# v0_1_0.net
KiCad netlist of a schematic drawn in EAGLE
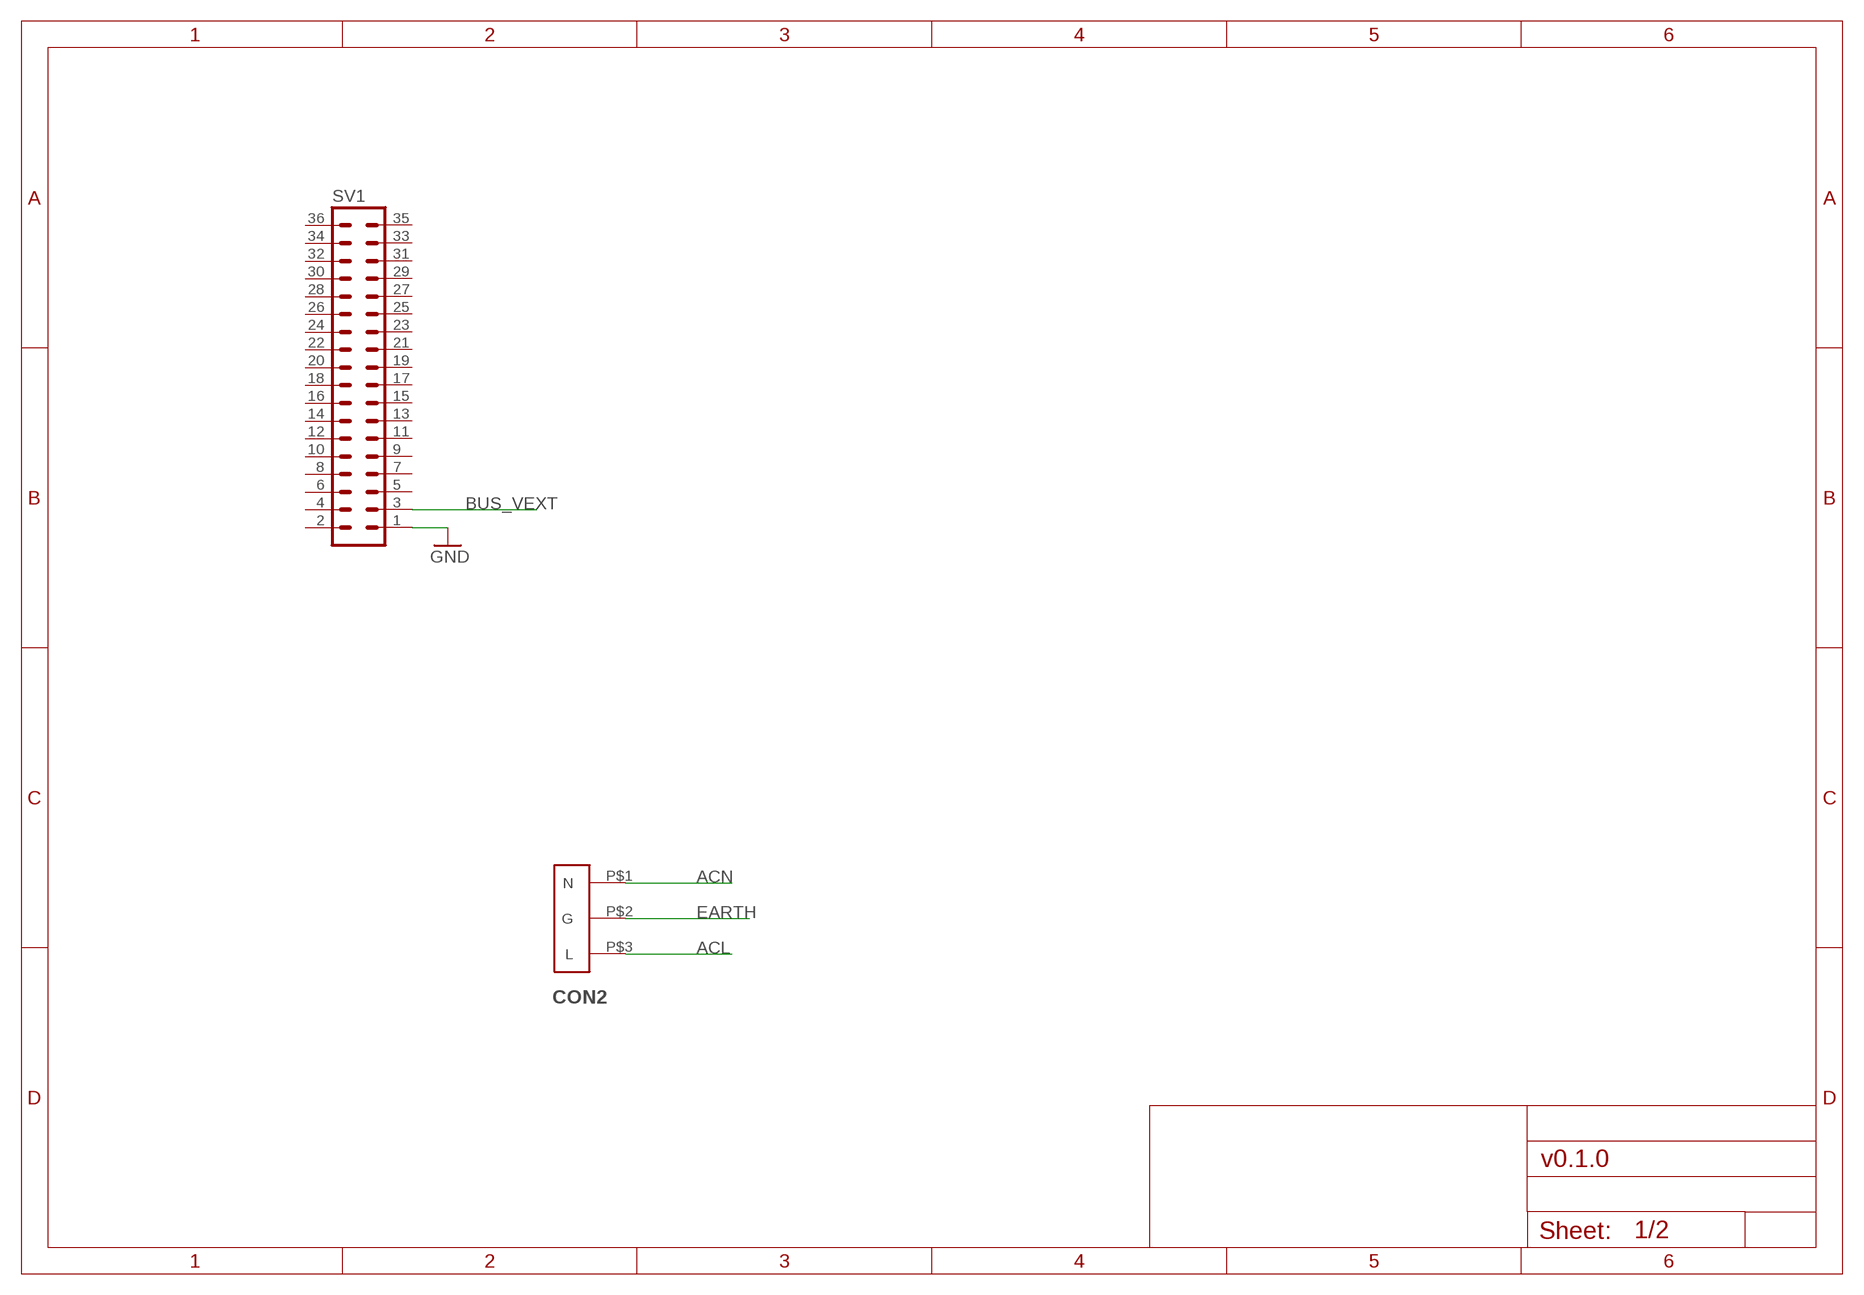
[diagram p0: schematic, sheet 1]
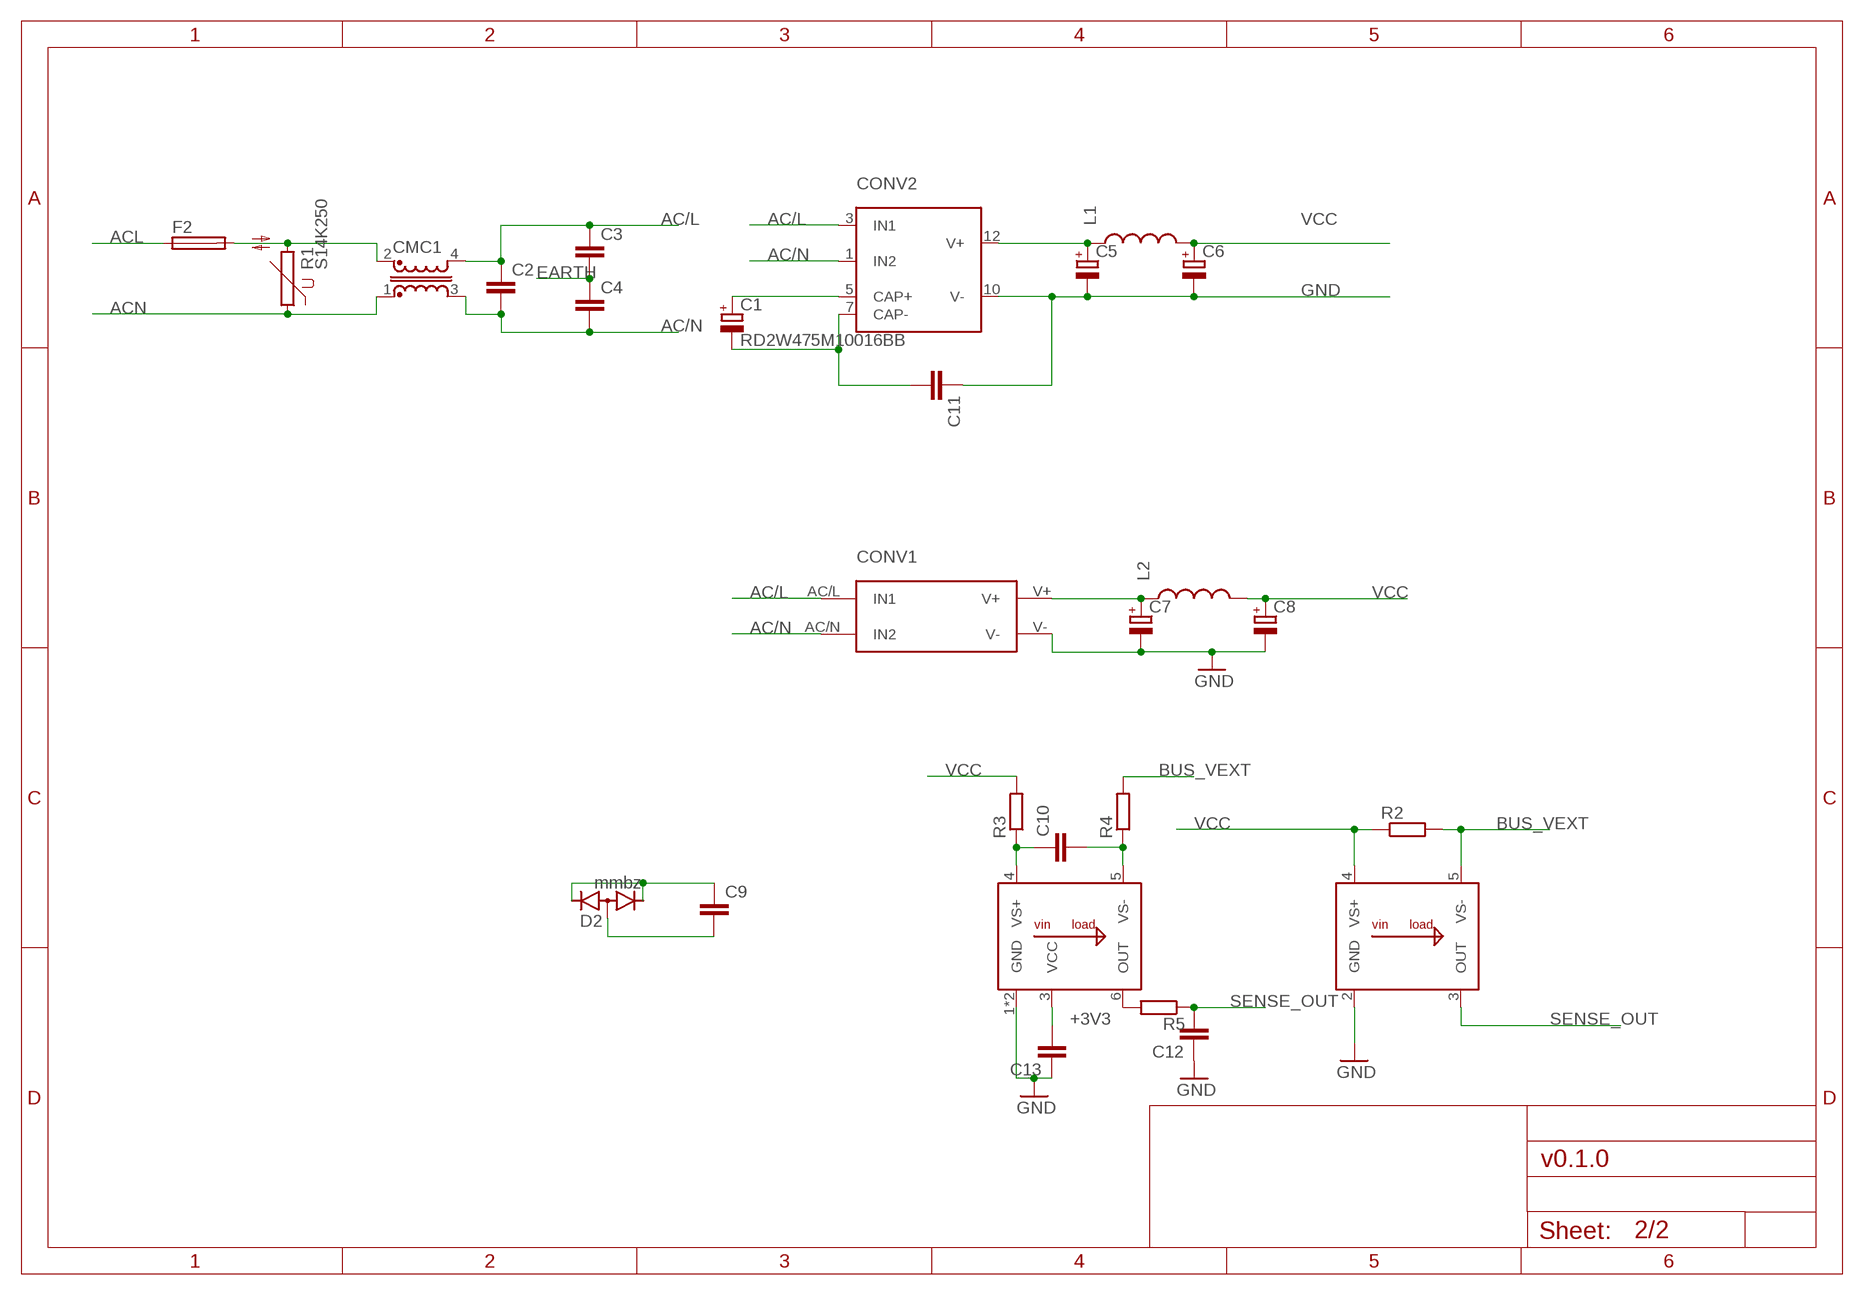
[diagram p1: schematic, sheet 2]

(export (version "E")
  (design (tool "Eeschema 10.0.6"))
  (components
    (comp (ref "C1")
      (value "RD2W475M10016BB")
      (footprint "eagle-import:E5-10,5")
      (libsource (lib "eagle-import") (part "CPOL-EUE5-10.5"))
    )
    (comp (ref "C2")
      (value "C-EUC1206")
      (footprint "eagle-import:C1206")
      (libsource (lib "eagle-import") (part "C-EUC1206"))
    )
    (comp (ref "C3")
      (value "C-EUC1206")
      (footprint "eagle-import:C1206")
      (libsource (lib "eagle-import") (part "C-EUC1206"))
    )
    (comp (ref "C4")
      (value "C-EUC1206")
      (footprint "eagle-import:C1206")
      (libsource (lib "eagle-import") (part "C-EUC1206"))
    )
    (comp (ref "C5")
      (value "CPOL-EUE5-10.5")
      (footprint "eagle-import:E5-10,5")
      (libsource (lib "eagle-import") (part "CPOL-EUE5-10.5"))
    )
    (comp (ref "C6")
      (value "CPOL-EUE5-10.5")
      (footprint "eagle-import:E5-10,5")
      (libsource (lib "eagle-import") (part "CPOL-EUE5-10.5"))
    )
    (comp (ref "C7")
      (value "CPOL-EUE5-10.5")
      (footprint "eagle-import:E5-10,5")
      (libsource (lib "eagle-import") (part "CPOL-EUE5-10.5"))
    )
    (comp (ref "C8")
      (value "CPOL-EUE5-10.5")
      (footprint "eagle-import:E5-10,5")
      (libsource (lib "eagle-import") (part "CPOL-EUE5-10.5"))
    )
    (comp (ref "C9")
      (value "C-EUC1206")
      (footprint "eagle-import:C1206")
      (libsource (lib "eagle-import") (part "C-EUC1206"))
    )
    (comp (ref "C10")
      (value "C-EUC0402")
      (footprint "eagle-import:C0402")
      (libsource (lib "eagle-import") (part "C-EUC0402"))
    )
    (comp (ref "C11")
      (value "C-EUC1206")
      (footprint "eagle-import:C1206")
      (libsource (lib "eagle-import") (part "C-EUC1206"))
    )
    (comp (ref "C12")
      (value "C-EUC0402")
      (footprint "eagle-import:C0402")
      (libsource (lib "eagle-import") (part "C-EUC0402"))
    )
    (comp (ref "C13")
      (value "C-EUC0402")
      (footprint "eagle-import:C0402")
      (libsource (lib "eagle-import") (part "C-EUC0402"))
    )
    (comp (ref "CMC1")
      (value "DLD-302U-1A")
      (footprint "eagle-import:DLD")
      (libsource (lib "eagle-import") (part "DLD-302U-1A"))
    )
    (comp (ref "CONV1")
      (value "IRM-03-12V")
      (footprint "eagle-import:IRM-03")
      (libsource (lib "eagle-import") (part "IRM-03-12V"))
    )
    (comp (ref "CONV2")
      (value "AMEOF312SJZ")
      (footprint "eagle-import:AMEOF3-JZ")
      (libsource (lib "eagle-import") (part "AMEOF312SJZ"))
    )
    (comp (ref "D2")
      (value "mmbz")
      (footprint "eagle-import:SOT23")
      (libsource (lib "eagle-import") (part "DIODE-2CA|ACSOT23"))
    )
    (comp (ref "F2")
      (value "ZH8")
      (footprint "eagle-import:ZH8X2")
      (libsource (lib "eagle-import") (part "ZH8"))
    )
    (comp (ref "IC1")
      (value "ZXCT1021")
      (footprint "eagle-import:SOT95P240X110-5")
      (libsource (lib "eagle-import") (part "ZXCT1021"))
    )
    (comp (ref "IC2")
      (value "BQ500100")
      (footprint "eagle-import:SC70-6")
      (libsource (lib "eagle-import") (part "BQ500100"))
    )
    (comp (ref "L1")
      (value "COIL0608-0.022")
      (footprint "eagle-import:COIL0608")
      (libsource (lib "eagle-import") (part "COIL0608-0.022"))
    )
    (comp (ref "L2")
      (value "COIL0608-0.022")
      (footprint "eagle-import:COIL0608")
      (libsource (lib "eagle-import") (part "COIL0608-0.022"))
    )
    (comp (ref "R1")
      (value "S14K250")
      (footprint "eagle-import:S14K250")
      (libsource (lib "eagle-import") (part "S14K250"))
    )
    (comp (ref "R2")
      (value "R-EU_R0805")
      (footprint "eagle-import:R0805")
      (libsource (lib "eagle-import") (part "R-EU_R0805"))
    )
    (comp (ref "R3")
      (value "R-EU_R0402")
      (footprint "eagle-import:R0402")
      (libsource (lib "eagle-import") (part "R-EU_R0402"))
    )
    (comp (ref "R4")
      (value "R-EU_R0402")
      (footprint "eagle-import:R0402")
      (libsource (lib "eagle-import") (part "R-EU_R0402"))
    )
    (comp (ref "R5")
      (value "R-EU_R0402")
      (footprint "eagle-import:R0402")
      (libsource (lib "eagle-import") (part "R-EU_R0402"))
    )
    (comp (ref "CON2")
      (value "4300.0101")
      (footprint "eagle-import:IEC-C6")
      (libsource (lib "eagle-import") (part "4300.0101"))
    )
    (comp (ref "SV1")
      (value "MA18-2")
      (footprint "eagle-import:MA18-2")
      (libsource (lib "eagle-import") (part "MA18-2"))
    )
  )
  (nets
    (net (code "1") (name "+3V3") (class "Default")
      (node (ref "C13") (pin "2") (pinfunction "2_2") (pintype "passive"))
      (node (ref "IC2") (pin "3") (pinfunction "VCC_3") (pintype "bidirectional"))
    )
    (net (code "2") (name "ACL") (class "Default")
      (node (ref "CON2") (pin "P$3") (pinfunction "L_P$3") (pintype "bidirectional"))
      (node (ref "F2") (pin "1") (pinfunction "1_1") (pintype "passive"))
      (node (ref "F2") (pin "1A") (pinfunction "1_1A") (pintype "passive"))
    )
    (net (code "3") (name "ACN") (class "Default")
      (node (ref "CMC1") (pin "1") (pinfunction "1_1") (pintype "passive"))
      (node (ref "CON2") (pin "P$1") (pinfunction "N_P$1") (pintype "bidirectional"))
      (node (ref "R1") (pin "1") (pinfunction "1_1") (pintype "passive"))
    )
    (net (code "4") (name "AC{slash}L") (class "Default")
      (node (ref "C2") (pin "1") (pinfunction "1_1") (pintype "passive"))
      (node (ref "C3") (pin "1") (pinfunction "1_1") (pintype "passive"))
      (node (ref "CMC1") (pin "4") (pinfunction "4_4") (pintype "passive"))
      (node (ref "CONV1") (pin "AC/L") (pinfunction "IN1_AC/L") (pintype "bidirectional"))
      (node (ref "CONV2") (pin "3") (pinfunction "IN1_3") (pintype "bidirectional"))
    )
    (net (code "5") (name "AC{slash}N") (class "Default")
      (node (ref "C2") (pin "2") (pinfunction "2_2") (pintype "passive"))
      (node (ref "C4") (pin "2") (pinfunction "2_2") (pintype "passive"))
      (node (ref "CMC1") (pin "3") (pinfunction "3_3") (pintype "passive"))
      (node (ref "CONV1") (pin "AC/N") (pinfunction "IN2_AC/N") (pintype "bidirectional"))
      (node (ref "CONV2") (pin "1") (pinfunction "IN2_1") (pintype "bidirectional"))
    )
    (net (code "6") (name "BUS_VEXT") (class "Default")
      (node (ref "IC1") (pin "5") (pinfunction "VS-_5") (pintype "bidirectional"))
      (node (ref "R2") (pin "2") (pinfunction "2_2") (pintype "passive"))
      (node (ref "R4") (pin "2") (pinfunction "2_2") (pintype "passive"))
      (node (ref "SV1") (pin "3") (pinfunction "3_3") (pintype "passive"))
    )
    (net (code "7") (name "EARTH") (class "Default")
      (node (ref "C3") (pin "2") (pinfunction "2_2") (pintype "passive"))
      (node (ref "C4") (pin "1") (pinfunction "1_1") (pintype "passive"))
      (node (ref "CON2") (pin "P$2") (pinfunction "G_P$2") (pintype "bidirectional"))
    )
    (net (code "8") (name "GND") (class "Default")
      (node (ref "C11") (pin "1") (pinfunction "1_1") (pintype "passive"))
      (node (ref "C12") (pin "1") (pinfunction "1_1") (pintype "passive"))
      (node (ref "C13") (pin "1") (pinfunction "1_1") (pintype "passive"))
      (node (ref "C5") (pin "-") (pinfunction "-_-") (pintype "passive"))
      (node (ref "C6") (pin "-") (pinfunction "-_-") (pintype "passive"))
      (node (ref "C7") (pin "-") (pinfunction "-_-") (pintype "passive"))
      (node (ref "C8") (pin "-") (pinfunction "-_-") (pintype "passive"))
      (node (ref "CONV1") (pin "V-") (pinfunction "V-_V-") (pintype "bidirectional"))
      (node (ref "CONV2") (pin "10") (pinfunction "V-_10") (pintype "bidirectional"))
      (node (ref "IC1") (pin "2") (pinfunction "GND_2") (pintype "bidirectional"))
      (node (ref "IC2") (pin "1") (pinfunction "GND_1") (pintype "bidirectional"))
      (node (ref "IC2") (pin "2") (pinfunction "GND_2") (pintype "bidirectional"))
      (node (ref "SV1") (pin "1") (pinfunction "1_1") (pintype "passive"))
    )
    (net (code "9") (name "Net-(CMC1-Pad2)") (class "Default")
      (node (ref "CMC1") (pin "2") (pinfunction "2_2") (pintype "passive"))
      (node (ref "F2") (pin "2") (pinfunction "2_2") (pintype "passive"))
      (node (ref "F2") (pin "2A") (pinfunction "2_2A") (pintype "passive"))
      (node (ref "R1") (pin "2") (pinfunction "2_2") (pintype "passive"))
    )
    (net (code "10") (name "Net-(CONV2-CAP+)") (class "Default")
      (node (ref "C1") (pin "+") (pinfunction "+_+") (pintype "passive"))
      (node (ref "CONV2") (pin "5") (pinfunction "CAP+_5") (pintype "bidirectional"))
    )
    (net (code "11") (name "Net-(CONV2-CAP-)") (class "Default")
      (node (ref "C1") (pin "-") (pinfunction "-_-") (pintype "passive"))
      (node (ref "C11") (pin "2") (pinfunction "2_2") (pintype "passive"))
      (node (ref "CONV2") (pin "7") (pinfunction "CAP-_7") (pintype "bidirectional"))
    )
    (net (code "12") (name "Net-(CONV2-V+)") (class "Default")
      (node (ref "C5") (pin "+") (pinfunction "+_+") (pintype "passive"))
      (node (ref "CONV2") (pin "12") (pinfunction "V+_12") (pintype "bidirectional"))
      (node (ref "L1") (pin "P$1") (pinfunction "1_P$1") (pintype "passive"))
    )
    (net (code "13") (name "Net-(D2-A)") (class "Default")
      (node (ref "C9") (pin "2") (pinfunction "2_2") (pintype "passive"))
      (node (ref "D2") (pin "3") (pinfunction "A_3") (pintype "passive"))
    )
    (net (code "14") (name "Net-(D2-K1)") (class "Default")
      (node (ref "C9") (pin "1") (pinfunction "1_1") (pintype "passive"))
      (node (ref "D2") (pin "1") (pinfunction "K1_1") (pintype "passive"))
      (node (ref "D2") (pin "2") (pinfunction "K2_2") (pintype "passive"))
    )
    (net (code "15") (name "Net-(IC2-OUT)") (class "Default")
      (node (ref "IC2") (pin "6") (pinfunction "OUT_6") (pintype "bidirectional"))
      (node (ref "R5") (pin "2") (pinfunction "2_2") (pintype "passive"))
    )
    (net (code "16") (name "Net-(IC2-VS+)") (class "Default")
      (node (ref "C10") (pin "1") (pinfunction "1_1") (pintype "passive"))
      (node (ref "IC2") (pin "4") (pinfunction "VS+_4") (pintype "bidirectional"))
      (node (ref "R3") (pin "1") (pinfunction "1_1") (pintype "passive"))
    )
    (net (code "17") (name "Net-(IC2-VS-)") (class "Default")
      (node (ref "C10") (pin "2") (pinfunction "2_2") (pintype "passive"))
      (node (ref "IC2") (pin "5") (pinfunction "VS-_5") (pintype "bidirectional"))
      (node (ref "R4") (pin "1") (pinfunction "1_1") (pintype "passive"))
    )
    (net (code "18") (name "Net-(L2-1)") (class "Default")
      (node (ref "C7") (pin "+") (pinfunction "+_+") (pintype "passive"))
      (node (ref "CONV1") (pin "V+") (pinfunction "V+_V+") (pintype "bidirectional"))
      (node (ref "L2") (pin "P$1") (pinfunction "1_P$1") (pintype "passive"))
    )
    (net (code "19") (name "SENSE_OUT") (class "Default")
      (node (ref "C12") (pin "2") (pinfunction "2_2") (pintype "passive"))
      (node (ref "IC1") (pin "3") (pinfunction "OUT_3") (pintype "bidirectional"))
      (node (ref "R5") (pin "1") (pinfunction "1_1") (pintype "passive"))
    )
    (net (code "20") (name "VCC") (class "Default")
      (node (ref "C6") (pin "+") (pinfunction "+_+") (pintype "passive"))
      (node (ref "C8") (pin "+") (pinfunction "+_+") (pintype "passive"))
      (node (ref "IC1") (pin "4") (pinfunction "VS+_4") (pintype "bidirectional"))
      (node (ref "L1") (pin "P$2") (pinfunction "2_P$2") (pintype "passive"))
      (node (ref "L2") (pin "P$2") (pinfunction "2_P$2") (pintype "passive"))
      (node (ref "R2") (pin "1") (pinfunction "1_1") (pintype "passive"))
      (node (ref "R3") (pin "2") (pinfunction "2_2") (pintype "passive"))
    )
    (net (code "21") (name "unconnected-(SV1-Pad2)") (class "Default")
      (node (ref "SV1") (pin "2") (pinfunction "2_2") (pintype "passive"))
    )
    (net (code "22") (name "unconnected-(SV1-Pad4)") (class "Default")
      (node (ref "SV1") (pin "4") (pinfunction "4_4") (pintype "passive"))
    )
    (net (code "23") (name "unconnected-(SV1-Pad5)") (class "Default")
      (node (ref "SV1") (pin "5") (pinfunction "5_5") (pintype "passive"))
    )
    (net (code "24") (name "unconnected-(SV1-Pad6)") (class "Default")
      (node (ref "SV1") (pin "6") (pinfunction "6_6") (pintype "passive"))
    )
    (net (code "25") (name "unconnected-(SV1-Pad7)") (class "Default")
      (node (ref "SV1") (pin "7") (pinfunction "7_7") (pintype "passive"))
    )
    (net (code "26") (name "unconnected-(SV1-Pad8)") (class "Default")
      (node (ref "SV1") (pin "8") (pinfunction "8_8") (pintype "passive"))
    )
    (net (code "27") (name "unconnected-(SV1-Pad9)") (class "Default")
      (node (ref "SV1") (pin "9") (pinfunction "9_9") (pintype "passive"))
    )
    (net (code "28") (name "unconnected-(SV1-Pad10)") (class "Default")
      (node (ref "SV1") (pin "10") (pinfunction "10_10") (pintype "passive"))
    )
    (net (code "29") (name "unconnected-(SV1-Pad11)") (class "Default")
      (node (ref "SV1") (pin "11") (pinfunction "11_11") (pintype "passive"))
    )
    (net (code "30") (name "unconnected-(SV1-Pad12)") (class "Default")
      (node (ref "SV1") (pin "12") (pinfunction "12_12") (pintype "passive"))
    )
    (net (code "31") (name "unconnected-(SV1-Pad13)") (class "Default")
      (node (ref "SV1") (pin "13") (pinfunction "13_13") (pintype "passive"))
    )
    (net (code "32") (name "unconnected-(SV1-Pad14)") (class "Default")
      (node (ref "SV1") (pin "14") (pinfunction "14_14") (pintype "passive"))
    )
    (net (code "33") (name "unconnected-(SV1-Pad15)") (class "Default")
      (node (ref "SV1") (pin "15") (pinfunction "15_15") (pintype "passive"))
    )
    (net (code "34") (name "unconnected-(SV1-Pad16)") (class "Default")
      (node (ref "SV1") (pin "16") (pinfunction "16_16") (pintype "passive"))
    )
    (net (code "35") (name "unconnected-(SV1-Pad17)") (class "Default")
      (node (ref "SV1") (pin "17") (pinfunction "17_17") (pintype "passive"))
    )
    (net (code "36") (name "unconnected-(SV1-Pad18)") (class "Default")
      (node (ref "SV1") (pin "18") (pinfunction "18_18") (pintype "passive"))
    )
    (net (code "37") (name "unconnected-(SV1-Pad19)") (class "Default")
      (node (ref "SV1") (pin "19") (pinfunction "19_19") (pintype "passive"))
    )
    (net (code "38") (name "unconnected-(SV1-Pad20)") (class "Default")
      (node (ref "SV1") (pin "20") (pinfunction "20_20") (pintype "passive"))
    )
    (net (code "39") (name "unconnected-(SV1-Pad21)") (class "Default")
      (node (ref "SV1") (pin "21") (pinfunction "21_21") (pintype "passive"))
    )
    (net (code "40") (name "unconnected-(SV1-Pad22)") (class "Default")
      (node (ref "SV1") (pin "22") (pinfunction "22_22") (pintype "passive"))
    )
    (net (code "41") (name "unconnected-(SV1-Pad23)") (class "Default")
      (node (ref "SV1") (pin "23") (pinfunction "23_23") (pintype "passive"))
    )
    (net (code "42") (name "unconnected-(SV1-Pad24)") (class "Default")
      (node (ref "SV1") (pin "24") (pinfunction "24_24") (pintype "passive"))
    )
    (net (code "43") (name "unconnected-(SV1-Pad25)") (class "Default")
      (node (ref "SV1") (pin "25") (pinfunction "25_25") (pintype "passive"))
    )
    (net (code "44") (name "unconnected-(SV1-Pad26)") (class "Default")
      (node (ref "SV1") (pin "26") (pinfunction "26_26") (pintype "passive"))
    )
    (net (code "45") (name "unconnected-(SV1-Pad27)") (class "Default")
      (node (ref "SV1") (pin "27") (pinfunction "27_27") (pintype "passive"))
    )
    (net (code "46") (name "unconnected-(SV1-Pad28)") (class "Default")
      (node (ref "SV1") (pin "28") (pinfunction "28_28") (pintype "passive"))
    )
    (net (code "47") (name "unconnected-(SV1-Pad29)") (class "Default")
      (node (ref "SV1") (pin "29") (pinfunction "29_29") (pintype "passive"))
    )
    (net (code "48") (name "unconnected-(SV1-Pad30)") (class "Default")
      (node (ref "SV1") (pin "30") (pinfunction "30_30") (pintype "passive"))
    )
    (net (code "49") (name "unconnected-(SV1-Pad31)") (class "Default")
      (node (ref "SV1") (pin "31") (pinfunction "31_31") (pintype "passive"))
    )
    (net (code "50") (name "unconnected-(SV1-Pad32)") (class "Default")
      (node (ref "SV1") (pin "32") (pinfunction "32_32") (pintype "passive"))
    )
    (net (code "51") (name "unconnected-(SV1-Pad33)") (class "Default")
      (node (ref "SV1") (pin "33") (pinfunction "33_33") (pintype "passive"))
    )
    (net (code "52") (name "unconnected-(SV1-Pad34)") (class "Default")
      (node (ref "SV1") (pin "34") (pinfunction "34_34") (pintype "passive"))
    )
    (net (code "53") (name "unconnected-(SV1-Pad35)") (class "Default")
      (node (ref "SV1") (pin "35") (pinfunction "35_35") (pintype "passive"))
    )
    (net (code "54") (name "unconnected-(SV1-Pad36)") (class "Default")
      (node (ref "SV1") (pin "36") (pinfunction "36_36") (pintype "passive"))
    )
  )
)
